# IO-testing-mezzanine.net
KiCad netlist of a schematic drawn in Altium Designer
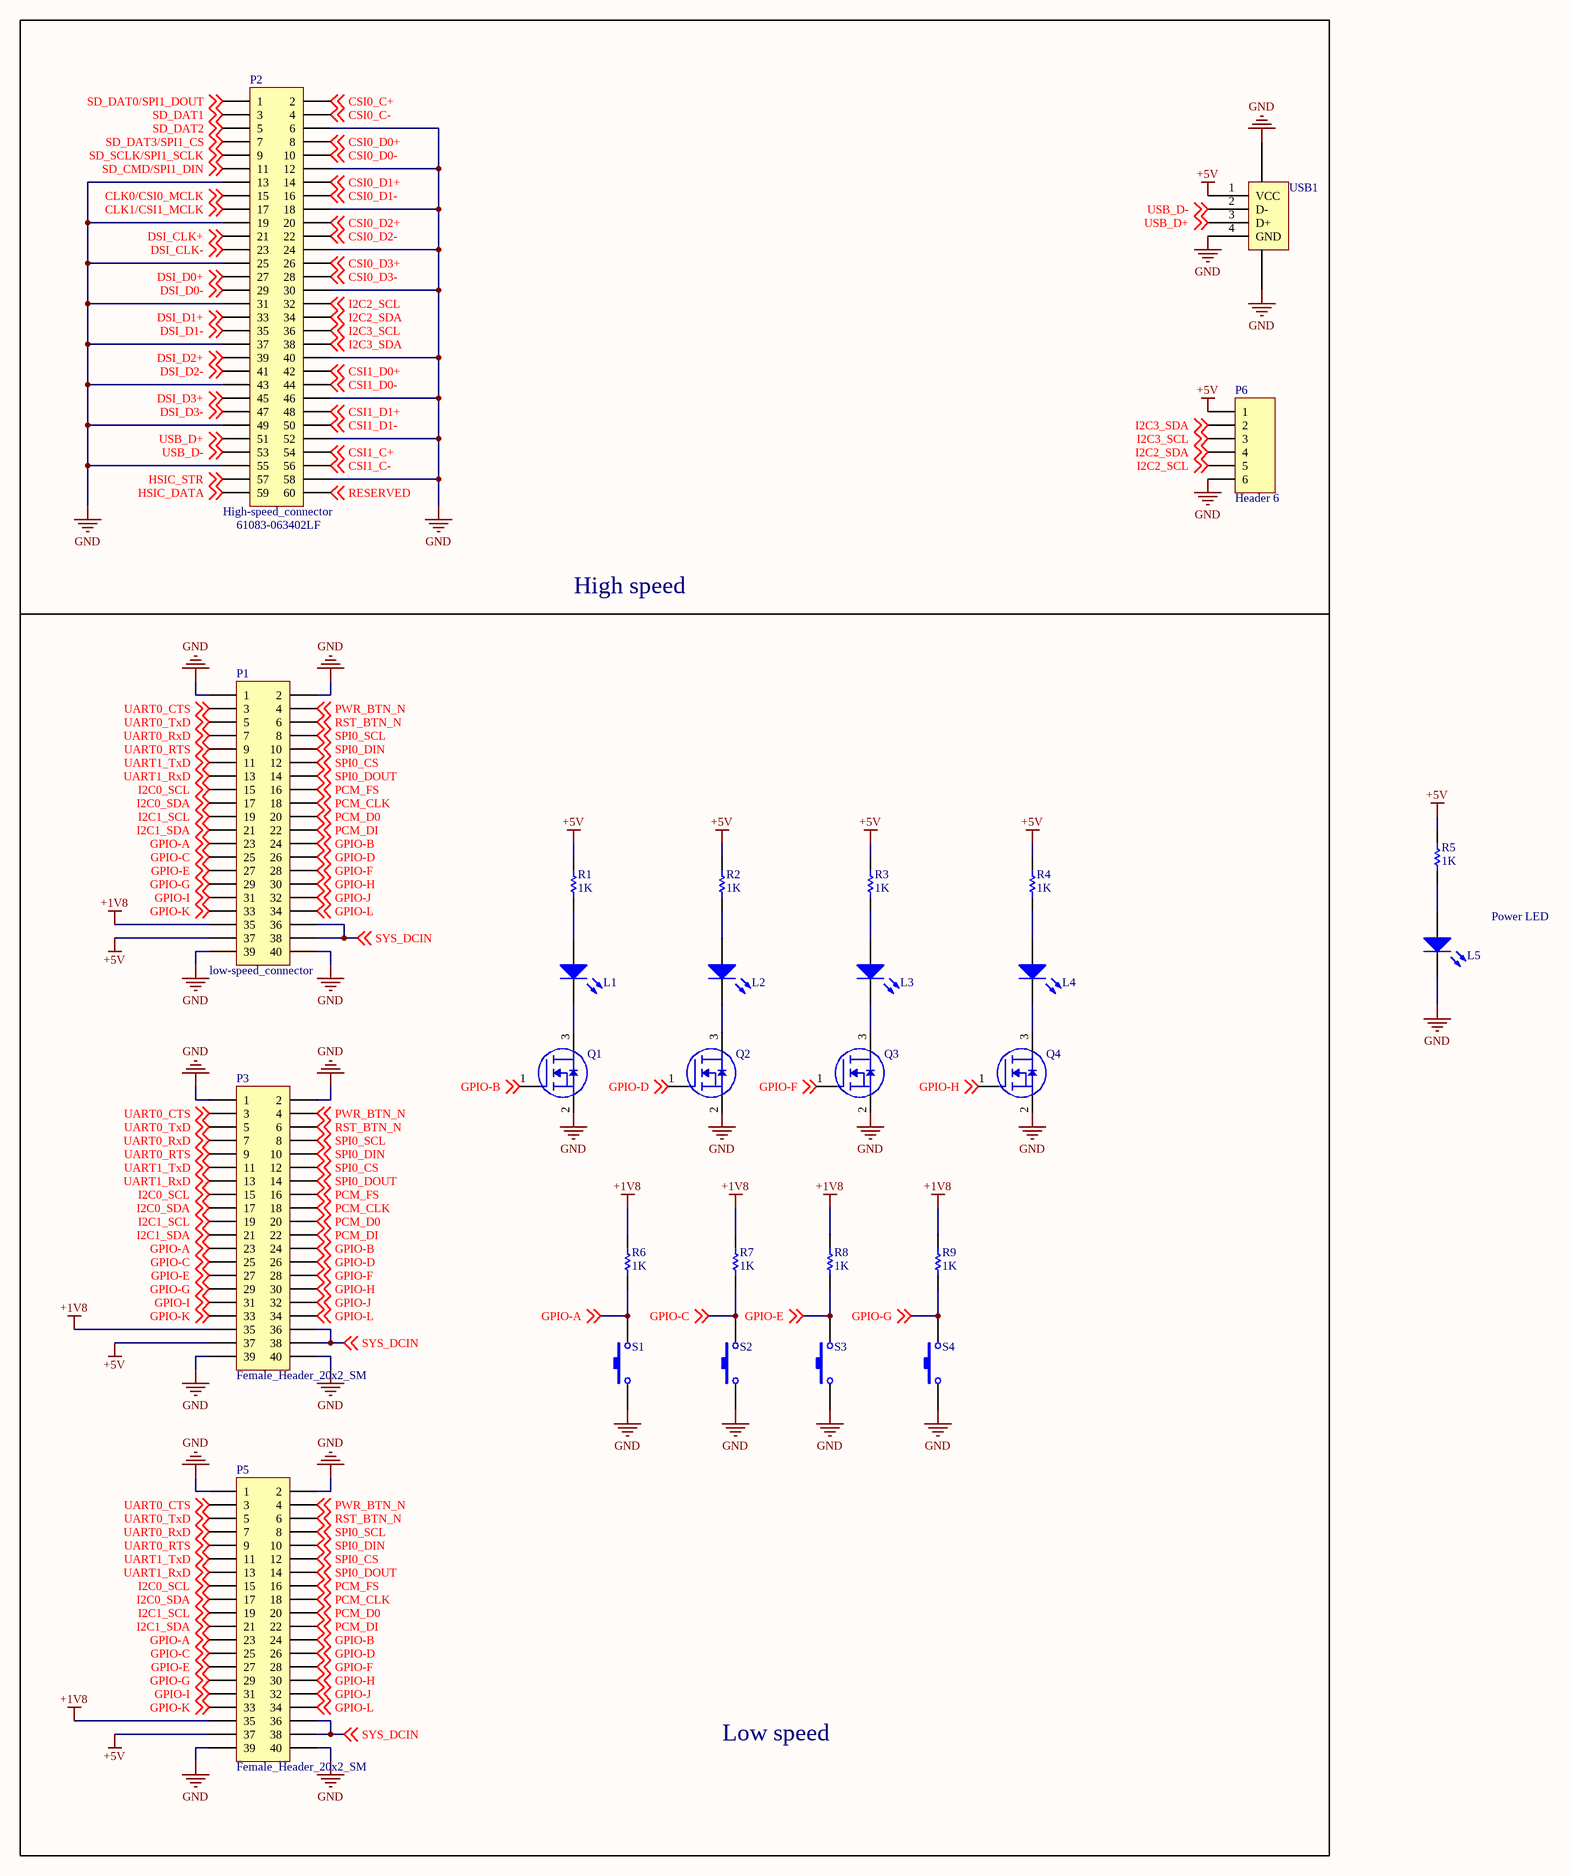
[diagram p0: IO-testing-mezzanine.SchDoc]

(export (version "E")
  (design (tool "Eeschema 10.0.6"))
  (components
    (comp (ref "L1")
      (value "~")
      (footprint "LED_0603")
      (description "LED BLUE CLEAR 0603 SMD")
      (fields
        (field (name "MANUFACTURER") "Lite-On Inc.")
        (field (name "MANUFACTURER PART NUMBER") "LTST-C193TBKT-5A")
      )
      (libsource (lib "IO-testing-mezzanine") (part "LTST-C193TBKT-5A"))
    )
    (comp (ref "L2")
      (value "~")
      (footprint "LED_0603")
      (description "LED BLUE CLEAR 0603 SMD")
      (fields
        (field (name "MANUFACTURER") "Lite-On Inc.")
        (field (name "MANUFACTURER PART NUMBER") "LTST-C193TBKT-5A")
      )
      (libsource (lib "IO-testing-mezzanine") (part "LTST-C193TBKT-5A"))
    )
    (comp (ref "L3")
      (value "~")
      (footprint "LED_0603")
      (description "LED BLUE CLEAR 0603 SMD")
      (fields
        (field (name "MANUFACTURER") "Lite-On Inc.")
        (field (name "MANUFACTURER PART NUMBER") "LTST-C193TBKT-5A")
      )
      (libsource (lib "IO-testing-mezzanine") (part "LTST-C193TBKT-5A"))
    )
    (comp (ref "L4")
      (value "~")
      (footprint "LED_0603")
      (description "LED BLUE CLEAR 0603 SMD")
      (fields
        (field (name "MANUFACTURER") "Lite-On Inc.")
        (field (name "MANUFACTURER PART NUMBER") "LTST-C193TBKT-5A")
      )
      (libsource (lib "IO-testing-mezzanine") (part "LTST-C193TBKT-5A"))
    )
    (comp (ref "L5")
      (value "~")
      (footprint "LED_0603")
      (description "LED BLUE CLEAR 0603 SMD")
      (fields
        (field (name "MANUFACTURER") "Lite-On Inc.")
        (field (name "MANUFACTURER PART NUMBER") "LTST-C193TBKT-5A")
      )
      (libsource (lib "IO-testing-mezzanine") (part "LTST-C193TBKT-5A"))
    )
    (comp (ref "P1")
      (value "low-speed_connector")
      (footprint "low-speed_connector_SM")
      (libsource (lib "mezza") (part "low-speed_connector"))
    )
    (comp (ref "P2")
      (value "High-speed_connector")
      (footprint "high-speed_connector")
      (fields (field (name "PARTNUMBER") "61083-063402LF"))
      (libsource (lib "mezza") (part "High-speed_connector"))
    )
    (comp (ref "P3")
      (value "Female_Header_20x2_SM")
      (footprint "Female_Header_20x2_SM")
      (libsource (lib "IO-testing-mezzanine") (part "Female_Header_20x2_SM"))
    )
    (comp (ref "P5")
      (value "Female_Header_20x2_SM")
      (footprint "low-speed_connector_SM_top")
      (libsource (lib "IO-testing-mezzanine") (part "Female_Header_20x2_SM"))
    )
    (comp (ref "P6")
      (value "Header 6")
      (footprint "HDR1X6")
      (description "Header, 6-Pin")
      (fields (field (name "PUBLISHER") "Altium Limited"))
      (libsource (lib "Miscellaneous Connectors") (part "Header 6"))
    )
    (comp (ref "Q1")
      (value "RUM002N05T2L")
      (footprint "SOT-723")
      (description "Nch 50V 200mA MOSFET")
      (libsource (lib "IO-testing-mezzanine") (part "RUM002N05T2L"))
    )
    (comp (ref "Q2")
      (value "RUM002N05T2L")
      (footprint "SOT-723")
      (description "Nch 50V 200mA MOSFET")
      (libsource (lib "IO-testing-mezzanine") (part "RUM002N05T2L"))
    )
    (comp (ref "Q3")
      (value "RUM002N05T2L")
      (footprint "SOT-723")
      (description "Nch 50V 200mA MOSFET")
      (libsource (lib "IO-testing-mezzanine") (part "RUM002N05T2L"))
    )
    (comp (ref "Q4")
      (value "RUM002N05T2L")
      (footprint "SOT-723")
      (description "Nch 50V 200mA MOSFET")
      (libsource (lib "IO-testing-mezzanine") (part "RUM002N05T2L"))
    )
    (comp (ref "R1")
      (value "1K")
      (footprint "0603")
      (description "Resistor")
      (fields
        (field (name "PARTNUMBER") "RC0603JR-071KL")
        (field (name "Comment") "Res1")
        (field (name "PUBLISHER") "Altium Limited")
      )
      (libsource (lib "IO-testing-mezzanine") (part "Res1"))
    )
    (comp (ref "R2")
      (value "1K")
      (footprint "0603")
      (description "Resistor")
      (fields
        (field (name "PARTNUMBER") "RC0603JR-071KL")
        (field (name "Comment") "Res1")
        (field (name "PUBLISHER") "Altium Limited")
      )
      (libsource (lib "IO-testing-mezzanine") (part "Res1"))
    )
    (comp (ref "R3")
      (value "1K")
      (footprint "0603")
      (description "Resistor")
      (fields
        (field (name "PARTNUMBER") "RC0603JR-071KL")
        (field (name "Comment") "Res1")
        (field (name "PUBLISHER") "Altium Limited")
      )
      (libsource (lib "IO-testing-mezzanine") (part "Res1"))
    )
    (comp (ref "R4")
      (value "1K")
      (footprint "0603")
      (description "Resistor")
      (fields
        (field (name "PARTNUMBER") "RC0603JR-071KL")
        (field (name "Comment") "Res1")
        (field (name "PUBLISHER") "Altium Limited")
      )
      (libsource (lib "IO-testing-mezzanine") (part "Res1"))
    )
    (comp (ref "R5")
      (value "1K")
      (footprint "0603")
      (description "Resistor")
      (fields
        (field (name "PARTNUMBER") "RC0603JR-071KL")
        (field (name "Comment") "Res1")
        (field (name "PUBLISHER") "Altium Limited")
      )
      (libsource (lib "IO-testing-mezzanine") (part "Res1"))
    )
    (comp (ref "R6")
      (value "1K")
      (footprint "0603")
      (description "Resistor")
      (fields
        (field (name "PARTNUMBER") "RC0603JR-071KL")
        (field (name "Comment") "Res1")
        (field (name "PUBLISHER") "Altium Limited")
      )
      (libsource (lib "IO-testing-mezzanine") (part "Res1"))
    )
    (comp (ref "R7")
      (value "1K")
      (footprint "0603")
      (description "Resistor")
      (fields
        (field (name "PARTNUMBER") "RC0603JR-071KL")
        (field (name "Comment") "Res1")
        (field (name "PUBLISHER") "Altium Limited")
      )
      (libsource (lib "IO-testing-mezzanine") (part "Res1"))
    )
    (comp (ref "R8")
      (value "1K")
      (footprint "0603")
      (description "Resistor")
      (fields
        (field (name "PARTNUMBER") "RC0603JR-071KL")
        (field (name "Comment") "Res1")
        (field (name "PUBLISHER") "Altium Limited")
      )
      (libsource (lib "IO-testing-mezzanine") (part "Res1"))
    )
    (comp (ref "R9")
      (value "1K")
      (footprint "0603")
      (description "Resistor")
      (fields
        (field (name "PARTNUMBER") "RC0603JR-071KL")
        (field (name "Comment") "Res1")
        (field (name "PUBLISHER") "Altium Limited")
      )
      (libsource (lib "IO-testing-mezzanine") (part "Res1"))
    )
    (comp (ref "S1")
      (value "SW-PB")
      (footprint "SW-PB")
      (description "Switch")
      (fields
        (field (name "MANUFACTURER") "C&K")
        (field (name "MANUFACTURER PART NUMBER") "KSR223GLFG")
        (field (name "PUBLISHER") "Altium Limited")
      )
      (libsource (lib "IO-testing-mezzanine") (part "SW-PB"))
    )
    (comp (ref "S2")
      (value "SW-PB")
      (footprint "SW-PB")
      (description "Switch")
      (fields
        (field (name "MANUFACTURER") "C&K")
        (field (name "MANUFACTURER PART NUMBER") "KSR223GLFG")
        (field (name "PUBLISHER") "Altium Limited")
      )
      (libsource (lib "IO-testing-mezzanine") (part "SW-PB"))
    )
    (comp (ref "S3")
      (value "SW-PB")
      (footprint "SW-PB")
      (description "Switch")
      (fields
        (field (name "MANUFACTURER") "C&K")
        (field (name "MANUFACTURER PART NUMBER") "KSR223GLFG")
        (field (name "PUBLISHER") "Altium Limited")
      )
      (libsource (lib "IO-testing-mezzanine") (part "SW-PB"))
    )
    (comp (ref "S4")
      (value "SW-PB")
      (footprint "SW-PB")
      (description "Switch")
      (fields
        (field (name "MANUFACTURER") "C&K")
        (field (name "MANUFACTURER PART NUMBER") "KSR223GLFG")
        (field (name "PUBLISHER") "Altium Limited")
      )
      (libsource (lib "IO-testing-mezzanine") (part "SW-PB"))
    )
    (comp (ref "USB1")
      (value "USB")
      (footprint "USB_a")
      (fields (field (name "PARTNUMBER") "USB-A-S-F-W-SM2") (field (name "MANUFACTURER") "Samtec Inc."))
      (libsource (lib "IO-testing-mezzanine") (part "USB"))
    )
  )
  (nets
    (net (code "1") (name "+1V8") (class "Default")
      (node (ref "P1") (pin "35") (pinfunction "35_35") (pintype "passive"))
      (node (ref "P3") (pin "35") (pinfunction "35_35") (pintype "passive"))
      (node (ref "P5") (pin "35") (pinfunction "35_35") (pintype "passive"))
      (node (ref "R6") (pin "2") (pinfunction "2_2") (pintype "passive"))
      (node (ref "R7") (pin "2") (pinfunction "2_2") (pintype "passive"))
      (node (ref "R8") (pin "2") (pinfunction "2_2") (pintype "passive"))
      (node (ref "R9") (pin "2") (pinfunction "2_2") (pintype "passive"))
    )
    (net (code "2") (name "+5V") (class "Default")
      (node (ref "P1") (pin "37") (pinfunction "37_37") (pintype "passive"))
      (node (ref "P3") (pin "37") (pinfunction "37_37") (pintype "passive"))
      (node (ref "P5") (pin "37") (pinfunction "37_37") (pintype "passive"))
      (node (ref "P6") (pin "1") (pinfunction "1_1") (pintype "passive"))
      (node (ref "R1") (pin "2") (pinfunction "2_2") (pintype "passive"))
      (node (ref "R2") (pin "2") (pinfunction "2_2") (pintype "passive"))
      (node (ref "R3") (pin "2") (pinfunction "2_2") (pintype "passive"))
      (node (ref "R4") (pin "2") (pinfunction "2_2") (pintype "passive"))
      (node (ref "R5") (pin "2") (pinfunction "2_2") (pintype "passive"))
      (node (ref "USB1") (pin "1") (pinfunction "VCC_1") (pintype "power_in"))
    )
    (net (code "3") (name "CLK0{slash}CSI0_MCLK") (class "Default")
      (node (ref "P2") (pin "15") (pinfunction "15_15") (pintype "passive"))
    )
    (net (code "4") (name "CLK1{slash}CSI1_MCLK") (class "Default")
      (node (ref "P2") (pin "17") (pinfunction "17_17") (pintype "passive"))
    )
    (net (code "5") (name "CSI0_C+") (class "Default")
      (node (ref "P2") (pin "2") (pinfunction "2_2") (pintype "passive"))
    )
    (net (code "6") (name "CSI0_C-") (class "Default")
      (node (ref "P2") (pin "4") (pinfunction "4_4") (pintype "passive"))
    )
    (net (code "7") (name "CSI0_D0+") (class "Default")
      (node (ref "P2") (pin "8") (pinfunction "8_8") (pintype "passive"))
    )
    (net (code "8") (name "CSI0_D0-") (class "Default")
      (node (ref "P2") (pin "10") (pinfunction "10_10") (pintype "passive"))
    )
    (net (code "9") (name "CSI0_D1+") (class "Default")
      (node (ref "P2") (pin "14") (pinfunction "14_14") (pintype "passive"))
    )
    (net (code "10") (name "CSI0_D1-") (class "Default")
      (node (ref "P2") (pin "16") (pinfunction "16_16") (pintype "passive"))
    )
    (net (code "11") (name "CSI0_D2+") (class "Default")
      (node (ref "P2") (pin "20") (pinfunction "20_20") (pintype "passive"))
    )
    (net (code "12") (name "CSI0_D2-") (class "Default")
      (node (ref "P2") (pin "22") (pinfunction "22_22") (pintype "passive"))
    )
    (net (code "13") (name "CSI0_D3+") (class "Default")
      (node (ref "P2") (pin "26") (pinfunction "26_26") (pintype "passive"))
    )
    (net (code "14") (name "CSI0_D3-") (class "Default")
      (node (ref "P2") (pin "28") (pinfunction "28_28") (pintype "passive"))
    )
    (net (code "15") (name "CSI1_C+") (class "Default")
      (node (ref "P2") (pin "54") (pinfunction "54_54") (pintype "passive"))
    )
    (net (code "16") (name "CSI1_C-") (class "Default")
      (node (ref "P2") (pin "56") (pinfunction "56_56") (pintype "passive"))
    )
    (net (code "17") (name "CSI1_D0+") (class "Default")
      (node (ref "P2") (pin "42") (pinfunction "42_42") (pintype "passive"))
    )
    (net (code "18") (name "CSI1_D0-") (class "Default")
      (node (ref "P2") (pin "44") (pinfunction "44_44") (pintype "passive"))
    )
    (net (code "19") (name "CSI1_D1+") (class "Default")
      (node (ref "P2") (pin "48") (pinfunction "48_48") (pintype "passive"))
    )
    (net (code "20") (name "CSI1_D1-") (class "Default")
      (node (ref "P2") (pin "50") (pinfunction "50_50") (pintype "passive"))
    )
    (net (code "21") (name "DSI_CLK+") (class "Default")
      (node (ref "P2") (pin "21") (pinfunction "21_21") (pintype "passive"))
    )
    (net (code "22") (name "DSI_CLK-") (class "Default")
      (node (ref "P2") (pin "23") (pinfunction "23_23") (pintype "passive"))
    )
    (net (code "23") (name "DSI_D0+") (class "Default")
      (node (ref "P2") (pin "27") (pinfunction "27_27") (pintype "passive"))
    )
    (net (code "24") (name "DSI_D0-") (class "Default")
      (node (ref "P2") (pin "29") (pinfunction "29_29") (pintype "passive"))
    )
    (net (code "25") (name "DSI_D1+") (class "Default")
      (node (ref "P2") (pin "33") (pinfunction "33_33") (pintype "passive"))
    )
    (net (code "26") (name "DSI_D1-") (class "Default")
      (node (ref "P2") (pin "35") (pinfunction "35_35") (pintype "passive"))
    )
    (net (code "27") (name "DSI_D2+") (class "Default")
      (node (ref "P2") (pin "39") (pinfunction "39_39") (pintype "passive"))
    )
    (net (code "28") (name "DSI_D2-") (class "Default")
      (node (ref "P2") (pin "41") (pinfunction "41_41") (pintype "passive"))
    )
    (net (code "29") (name "DSI_D3+") (class "Default")
      (node (ref "P2") (pin "45") (pinfunction "45_45") (pintype "passive"))
    )
    (net (code "30") (name "DSI_D3-") (class "Default")
      (node (ref "P2") (pin "47") (pinfunction "47_47") (pintype "passive"))
    )
    (net (code "31") (name "GND") (class "Default")
      (node (ref "L5") (pin "2") (pinfunction "K_2") (pintype "passive"))
      (node (ref "P1") (pin "1") (pinfunction "1_1") (pintype "passive"))
      (node (ref "P1") (pin "2") (pinfunction "2_2") (pintype "passive"))
      (node (ref "P1") (pin "39") (pinfunction "39_39") (pintype "passive"))
      (node (ref "P1") (pin "40") (pinfunction "40_40") (pintype "passive"))
      (node (ref "P2") (pin "12") (pinfunction "12_12") (pintype "passive"))
      (node (ref "P2") (pin "13") (pinfunction "13_13") (pintype "passive"))
      (node (ref "P2") (pin "18") (pinfunction "18_18") (pintype "passive"))
      (node (ref "P2") (pin "19") (pinfunction "19_19") (pintype "passive"))
      (node (ref "P2") (pin "24") (pinfunction "24_24") (pintype "passive"))
      (node (ref "P2") (pin "25") (pinfunction "25_25") (pintype "passive"))
      (node (ref "P2") (pin "30") (pinfunction "30_30") (pintype "passive"))
      (node (ref "P2") (pin "31") (pinfunction "31_31") (pintype "passive"))
      (node (ref "P2") (pin "37") (pinfunction "37_37") (pintype "passive"))
      (node (ref "P2") (pin "40") (pinfunction "40_40") (pintype "passive"))
      (node (ref "P2") (pin "43") (pinfunction "43_43") (pintype "passive"))
      (node (ref "P2") (pin "46") (pinfunction "46_46") (pintype "passive"))
      (node (ref "P2") (pin "49") (pinfunction "49_49") (pintype "passive"))
      (node (ref "P2") (pin "52") (pinfunction "52_52") (pintype "passive"))
      (node (ref "P2") (pin "55") (pinfunction "55_55") (pintype "passive"))
      (node (ref "P2") (pin "58") (pinfunction "58_58") (pintype "passive"))
      (node (ref "P2") (pin "6") (pinfunction "6_6") (pintype "passive"))
      (node (ref "P3") (pin "1") (pinfunction "1_1") (pintype "passive"))
      (node (ref "P3") (pin "2") (pinfunction "2_2") (pintype "passive"))
      (node (ref "P3") (pin "39") (pinfunction "39_39") (pintype "passive"))
      (node (ref "P3") (pin "40") (pinfunction "40_40") (pintype "passive"))
      (node (ref "P5") (pin "1") (pinfunction "1_1") (pintype "passive"))
      (node (ref "P5") (pin "2") (pinfunction "2_2") (pintype "passive"))
      (node (ref "P5") (pin "39") (pinfunction "39_39") (pintype "passive"))
      (node (ref "P5") (pin "40") (pinfunction "40_40") (pintype "passive"))
      (node (ref "P6") (pin "6") (pinfunction "6_6") (pintype "passive"))
      (node (ref "Q1") (pin "2") (pinfunction "S_2") (pintype "passive"))
      (node (ref "Q2") (pin "2") (pinfunction "S_2") (pintype "passive"))
      (node (ref "Q3") (pin "2") (pinfunction "S_2") (pintype "passive"))
      (node (ref "Q4") (pin "2") (pinfunction "S_2") (pintype "passive"))
      (node (ref "S1") (pin "1") (pinfunction "1_1") (pintype "passive"))
      (node (ref "S2") (pin "1") (pinfunction "1_1") (pintype "passive"))
      (node (ref "S3") (pin "1") (pinfunction "1_1") (pintype "passive"))
      (node (ref "S4") (pin "1") (pinfunction "1_1") (pintype "passive"))
      (node (ref "USB1") (pin "4") (pinfunction "GND_4") (pintype "power_in"))
      (node (ref "USB1") (pin "5") (pinfunction "GND_5") (pintype "power_in"))
      (node (ref "USB1") (pin "6") (pinfunction "GND_6") (pintype "power_in"))
    )
    (net (code "32") (name "GPIO-A") (class "Default")
      (node (ref "P1") (pin "23") (pinfunction "23_23") (pintype "passive"))
      (node (ref "P3") (pin "23") (pinfunction "23_23") (pintype "passive"))
      (node (ref "P5") (pin "23") (pinfunction "23_23") (pintype "passive"))
      (node (ref "R6") (pin "1") (pinfunction "1_1") (pintype "passive"))
      (node (ref "S1") (pin "2") (pinfunction "2_2") (pintype "passive"))
    )
    (net (code "33") (name "GPIO-B") (class "Default")
      (node (ref "P1") (pin "24") (pinfunction "24_24") (pintype "passive"))
      (node (ref "P3") (pin "24") (pinfunction "24_24") (pintype "passive"))
      (node (ref "P5") (pin "24") (pinfunction "24_24") (pintype "passive"))
      (node (ref "Q1") (pin "1") (pinfunction "G_1") (pintype "passive"))
    )
    (net (code "34") (name "GPIO-C") (class "Default")
      (node (ref "P1") (pin "25") (pinfunction "25_25") (pintype "passive"))
      (node (ref "P3") (pin "25") (pinfunction "25_25") (pintype "passive"))
      (node (ref "P5") (pin "25") (pinfunction "25_25") (pintype "passive"))
      (node (ref "R7") (pin "1") (pinfunction "1_1") (pintype "passive"))
      (node (ref "S2") (pin "2") (pinfunction "2_2") (pintype "passive"))
    )
    (net (code "35") (name "GPIO-D") (class "Default")
      (node (ref "P1") (pin "26") (pinfunction "26_26") (pintype "passive"))
      (node (ref "P3") (pin "26") (pinfunction "26_26") (pintype "passive"))
      (node (ref "P5") (pin "26") (pinfunction "26_26") (pintype "passive"))
      (node (ref "Q2") (pin "1") (pinfunction "G_1") (pintype "passive"))
    )
    (net (code "36") (name "GPIO-E") (class "Default")
      (node (ref "P1") (pin "27") (pinfunction "27_27") (pintype "passive"))
      (node (ref "P3") (pin "27") (pinfunction "27_27") (pintype "passive"))
      (node (ref "P5") (pin "27") (pinfunction "27_27") (pintype "passive"))
      (node (ref "R8") (pin "1") (pinfunction "1_1") (pintype "passive"))
      (node (ref "S3") (pin "2") (pinfunction "2_2") (pintype "passive"))
    )
    (net (code "37") (name "GPIO-F") (class "Default")
      (node (ref "P1") (pin "28") (pinfunction "28_28") (pintype "passive"))
      (node (ref "P3") (pin "28") (pinfunction "28_28") (pintype "passive"))
      (node (ref "P5") (pin "28") (pinfunction "28_28") (pintype "passive"))
      (node (ref "Q3") (pin "1") (pinfunction "G_1") (pintype "passive"))
    )
    (net (code "38") (name "GPIO-G") (class "Default")
      (node (ref "P1") (pin "29") (pinfunction "29_29") (pintype "passive"))
      (node (ref "P3") (pin "29") (pinfunction "29_29") (pintype "passive"))
      (node (ref "P5") (pin "29") (pinfunction "29_29") (pintype "passive"))
      (node (ref "R9") (pin "1") (pinfunction "1_1") (pintype "passive"))
      (node (ref "S4") (pin "2") (pinfunction "2_2") (pintype "passive"))
    )
    (net (code "39") (name "GPIO-H") (class "Default")
      (node (ref "P1") (pin "30") (pinfunction "30_30") (pintype "passive"))
      (node (ref "P3") (pin "30") (pinfunction "30_30") (pintype "passive"))
      (node (ref "P5") (pin "30") (pinfunction "30_30") (pintype "passive"))
      (node (ref "Q4") (pin "1") (pinfunction "G_1") (pintype "passive"))
    )
    (net (code "40") (name "GPIO-I") (class "Default")
      (node (ref "P1") (pin "31") (pinfunction "31_31") (pintype "passive"))
      (node (ref "P3") (pin "31") (pinfunction "31_31") (pintype "passive"))
      (node (ref "P5") (pin "31") (pinfunction "31_31") (pintype "passive"))
    )
    (net (code "41") (name "GPIO-J") (class "Default")
      (node (ref "P1") (pin "32") (pinfunction "32_32") (pintype "passive"))
      (node (ref "P3") (pin "32") (pinfunction "32_32") (pintype "passive"))
      (node (ref "P5") (pin "32") (pinfunction "32_32") (pintype "passive"))
    )
    (net (code "42") (name "GPIO-K") (class "Default")
      (node (ref "P1") (pin "33") (pinfunction "33_33") (pintype "passive"))
      (node (ref "P3") (pin "33") (pinfunction "33_33") (pintype "passive"))
      (node (ref "P5") (pin "33") (pinfunction "33_33") (pintype "passive"))
    )
    (net (code "43") (name "GPIO-L") (class "Default")
      (node (ref "P1") (pin "34") (pinfunction "34_34") (pintype "passive"))
      (node (ref "P3") (pin "34") (pinfunction "34_34") (pintype "passive"))
      (node (ref "P5") (pin "34") (pinfunction "34_34") (pintype "passive"))
    )
    (net (code "44") (name "HSIC_DATA") (class "Default")
      (node (ref "P2") (pin "59") (pinfunction "59_59") (pintype "passive"))
    )
    (net (code "45") (name "HSIC_STR") (class "Default")
      (node (ref "P2") (pin "39") (pinfunction "57_39") (pintype "passive"))
    )
    (net (code "46") (name "I2C0_SCL") (class "Default")
      (node (ref "P1") (pin "15") (pinfunction "15_15") (pintype "passive"))
      (node (ref "P3") (pin "15") (pinfunction "15_15") (pintype "passive"))
      (node (ref "P5") (pin "15") (pinfunction "15_15") (pintype "passive"))
    )
    (net (code "47") (name "I2C0_SDA") (class "Default")
      (node (ref "P1") (pin "17") (pinfunction "17_17") (pintype "passive"))
      (node (ref "P3") (pin "17") (pinfunction "17_17") (pintype "passive"))
      (node (ref "P5") (pin "17") (pinfunction "17_17") (pintype "passive"))
    )
    (net (code "48") (name "I2C1_SCL") (class "Default")
      (node (ref "P1") (pin "19") (pinfunction "19_19") (pintype "passive"))
      (node (ref "P3") (pin "19") (pinfunction "19_19") (pintype "passive"))
      (node (ref "P5") (pin "19") (pinfunction "19_19") (pintype "passive"))
    )
    (net (code "49") (name "I2C1_SDA") (class "Default")
      (node (ref "P1") (pin "21") (pinfunction "21_21") (pintype "passive"))
      (node (ref "P3") (pin "21") (pinfunction "21_21") (pintype "passive"))
      (node (ref "P5") (pin "21") (pinfunction "21_21") (pintype "passive"))
    )
    (net (code "50") (name "I2C2_SCL") (class "Default")
      (node (ref "P2") (pin "32") (pinfunction "32_32") (pintype "passive"))
      (node (ref "P6") (pin "5") (pinfunction "5_5") (pintype "passive"))
    )
    (net (code "51") (name "I2C2_SDA") (class "Default")
      (node (ref "P2") (pin "34") (pinfunction "34_34") (pintype "passive"))
      (node (ref "P6") (pin "4") (pinfunction "4_4") (pintype "passive"))
    )
    (net (code "52") (name "I2C3_SCL") (class "Default")
      (node (ref "P2") (pin "36") (pinfunction "36_36") (pintype "passive"))
      (node (ref "P6") (pin "3") (pinfunction "3_3") (pintype "passive"))
    )
    (net (code "53") (name "I2C3_SDA") (class "Default")
      (node (ref "P2") (pin "38") (pinfunction "38_38") (pintype "passive"))
      (node (ref "P6") (pin "2") (pinfunction "2_2") (pintype "passive"))
    )
    (net (code "54") (name "Net-(L1-A)") (class "Default")
      (node (ref "L1") (pin "1") (pinfunction "A_1") (pintype "passive"))
      (node (ref "R1") (pin "1") (pinfunction "1_1") (pintype "passive"))
    )
    (net (code "55") (name "Net-(L1-K)") (class "Default")
      (node (ref "L1") (pin "2") (pinfunction "K_2") (pintype "passive"))
      (node (ref "Q1") (pin "3") (pinfunction "D_3") (pintype "passive"))
    )
    (net (code "56") (name "Net-(L2-A)") (class "Default")
      (node (ref "L2") (pin "1") (pinfunction "A_1") (pintype "passive"))
      (node (ref "R2") (pin "1") (pinfunction "1_1") (pintype "passive"))
    )
    (net (code "57") (name "Net-(L2-K)") (class "Default")
      (node (ref "L2") (pin "2") (pinfunction "K_2") (pintype "passive"))
      (node (ref "Q2") (pin "3") (pinfunction "D_3") (pintype "passive"))
    )
    (net (code "58") (name "Net-(L3-A)") (class "Default")
      (node (ref "L3") (pin "1") (pinfunction "A_1") (pintype "passive"))
      (node (ref "R3") (pin "1") (pinfunction "1_1") (pintype "passive"))
    )
    (net (code "59") (name "Net-(L3-K)") (class "Default")
      (node (ref "L3") (pin "2") (pinfunction "K_2") (pintype "passive"))
      (node (ref "Q3") (pin "3") (pinfunction "D_3") (pintype "passive"))
    )
    (net (code "60") (name "Net-(L4-A)") (class "Default")
      (node (ref "L4") (pin "1") (pinfunction "A_1") (pintype "passive"))
      (node (ref "R4") (pin "1") (pinfunction "1_1") (pintype "passive"))
    )
    (net (code "61") (name "Net-(L4-K)") (class "Default")
      (node (ref "L4") (pin "2") (pinfunction "K_2") (pintype "passive"))
      (node (ref "Q4") (pin "3") (pinfunction "D_3") (pintype "passive"))
    )
    (net (code "62") (name "Net-(L5-A)") (class "Default")
      (node (ref "L5") (pin "1") (pinfunction "A_1") (pintype "passive"))
      (node (ref "R5") (pin "1") (pinfunction "1_1") (pintype "passive"))
    )
    (net (code "63") (name "PCM_CLK") (class "Default")
      (node (ref "P1") (pin "18") (pinfunction "18_18") (pintype "passive"))
      (node (ref "P3") (pin "18") (pinfunction "18_18") (pintype "passive"))
      (node (ref "P5") (pin "18") (pinfunction "18_18") (pintype "passive"))
    )
    (net (code "64") (name "PCM_D0") (class "Default")
      (node (ref "P1") (pin "20") (pinfunction "20_20") (pintype "passive"))
      (node (ref "P3") (pin "20") (pinfunction "20_20") (pintype "passive"))
      (node (ref "P5") (pin "20") (pinfunction "20_20") (pintype "passive"))
    )
    (net (code "65") (name "PCM_DI") (class "Default")
      (node (ref "P1") (pin "22") (pinfunction "22_22") (pintype "passive"))
      (node (ref "P3") (pin "22") (pinfunction "22_22") (pintype "passive"))
      (node (ref "P5") (pin "22") (pinfunction "22_22") (pintype "passive"))
    )
    (net (code "66") (name "PCM_FS") (class "Default")
      (node (ref "P1") (pin "16") (pinfunction "16_16") (pintype "passive"))
      (node (ref "P3") (pin "16") (pinfunction "16_16") (pintype "passive"))
      (node (ref "P5") (pin "16") (pinfunction "16_16") (pintype "passive"))
    )
    (net (code "67") (name "PWR_BTN_N") (class "Default")
      (node (ref "P1") (pin "4") (pinfunction "4_4") (pintype "passive"))
      (node (ref "P3") (pin "4") (pinfunction "4_4") (pintype "passive"))
      (node (ref "P5") (pin "4") (pinfunction "4_4") (pintype "passive"))
    )
    (net (code "68") (name "RESERVED") (class "Default")
      (node (ref "P2") (pin "38") (pinfunction "60_38") (pintype "passive"))
    )
    (net (code "69") (name "RST_BTN_N") (class "Default")
      (node (ref "P1") (pin "6") (pinfunction "6_6") (pintype "passive"))
      (node (ref "P3") (pin "6") (pinfunction "6_6") (pintype "passive"))
      (node (ref "P5") (pin "6") (pinfunction "6_6") (pintype "passive"))
    )
    (net (code "70") (name "SD_CMD{slash}SPI1_DIN") (class "Default")
      (node (ref "P2") (pin "11") (pinfunction "11_11") (pintype "passive"))
    )
    (net (code "71") (name "SD_DAT0{slash}SPI1_DOUT") (class "Default")
      (node (ref "P2") (pin "1") (pinfunction "1_1") (pintype "passive"))
    )
    (net (code "72") (name "SD_DAT1") (class "Default")
      (node (ref "P2") (pin "3") (pinfunction "3_3") (pintype "passive"))
    )
    (net (code "73") (name "SD_DAT2") (class "Default")
      (node (ref "P2") (pin "5") (pinfunction "5_5") (pintype "passive"))
    )
    (net (code "74") (name "SD_DAT3{slash}SPI1_CS") (class "Default")
      (node (ref "P2") (pin "7") (pinfunction "7_7") (pintype "passive"))
    )
    (net (code "75") (name "SD_SCLK{slash}SPI1_SCLK") (class "Default")
      (node (ref "P2") (pin "9") (pinfunction "9_9") (pintype "passive"))
    )
    (net (code "76") (name "SPI0_CS") (class "Default")
      (node (ref "P1") (pin "12") (pinfunction "12_12") (pintype "passive"))
      (node (ref "P3") (pin "12") (pinfunction "12_12") (pintype "passive"))
      (node (ref "P5") (pin "12") (pinfunction "12_12") (pintype "passive"))
    )
    (net (code "77") (name "SPI0_DIN") (class "Default")
      (node (ref "P1") (pin "10") (pinfunction "10_10") (pintype "passive"))
      (node (ref "P3") (pin "10") (pinfunction "10_10") (pintype "passive"))
      (node (ref "P5") (pin "10") (pinfunction "10_10") (pintype "passive"))
    )
    (net (code "78") (name "SPI0_DOUT") (class "Default")
      (node (ref "P1") (pin "14") (pinfunction "14_14") (pintype "passive"))
      (node (ref "P3") (pin "14") (pinfunction "14_14") (pintype "passive"))
      (node (ref "P5") (pin "14") (pinfunction "14_14") (pintype "passive"))
    )
    (net (code "79") (name "SPI0_SCL") (class "Default")
      (node (ref "P1") (pin "8") (pinfunction "8_8") (pintype "passive"))
      (node (ref "P3") (pin "8") (pinfunction "8_8") (pintype "passive"))
      (node (ref "P5") (pin "8") (pinfunction "8_8") (pintype "passive"))
    )
    (net (code "80") (name "SYS_DCIN") (class "Default")
      (node (ref "P1") (pin "36") (pinfunction "36_36") (pintype "passive"))
      (node (ref "P1") (pin "38") (pinfunction "38_38") (pintype "passive"))
      (node (ref "P3") (pin "36") (pinfunction "36_36") (pintype "passive"))
      (node (ref "P3") (pin "38") (pinfunction "38_38") (pintype "passive"))
      (node (ref "P5") (pin "36") (pinfunction "36_36") (pintype "passive"))
      (node (ref "P5") (pin "38") (pinfunction "38_38") (pintype "passive"))
    )
    (net (code "81") (name "UART0_CTS") (class "Default")
      (node (ref "P1") (pin "3") (pinfunction "3_3") (pintype "passive"))
      (node (ref "P3") (pin "3") (pinfunction "3_3") (pintype "passive"))
      (node (ref "P5") (pin "3") (pinfunction "3_3") (pintype "passive"))
    )
    (net (code "82") (name "UART0_RTS") (class "Default")
      (node (ref "P1") (pin "9") (pinfunction "9_9") (pintype "passive"))
      (node (ref "P3") (pin "9") (pinfunction "9_9") (pintype "passive"))
      (node (ref "P5") (pin "9") (pinfunction "9_9") (pintype "passive"))
    )
    (net (code "83") (name "UART0_RxD") (class "Default")
      (node (ref "P1") (pin "7") (pinfunction "7_7") (pintype "passive"))
      (node (ref "P3") (pin "7") (pinfunction "7_7") (pintype "passive"))
      (node (ref "P5") (pin "7") (pinfunction "7_7") (pintype "passive"))
    )
    (net (code "84") (name "UART0_TxD") (class "Default")
      (node (ref "P1") (pin "5") (pinfunction "5_5") (pintype "passive"))
      (node (ref "P3") (pin "5") (pinfunction "5_5") (pintype "passive"))
      (node (ref "P5") (pin "5") (pinfunction "5_5") (pintype "passive"))
    )
    (net (code "85") (name "UART1_RxD") (class "Default")
      (node (ref "P1") (pin "13") (pinfunction "13_13") (pintype "passive"))
      (node (ref "P3") (pin "13") (pinfunction "13_13") (pintype "passive"))
      (node (ref "P5") (pin "13") (pinfunction "13_13") (pintype "passive"))
    )
    (net (code "86") (name "UART1_TxD") (class "Default")
      (node (ref "P1") (pin "11") (pinfunction "11_11") (pintype "passive"))
      (node (ref "P3") (pin "11") (pinfunction "11_11") (pintype "passive"))
      (node (ref "P5") (pin "11") (pinfunction "11_11") (pintype "passive"))
    )
    (net (code "87") (name "USB_D+") (class "Default")
      (node (ref "P2") (pin "51") (pinfunction "51_51") (pintype "passive"))
      (node (ref "USB1") (pin "3") (pinfunction "D+_3") (pintype "passive"))
    )
    (net (code "88") (name "USB_D-") (class "Default")
      (node (ref "P2") (pin "53") (pinfunction "53_53") (pintype "passive"))
      (node (ref "USB1") (pin "2") (pinfunction "D-_2") (pintype "passive"))
    )
  )
)
